# De_Embed.net
KiCad netlist of a schematic drawn in Altium Designer
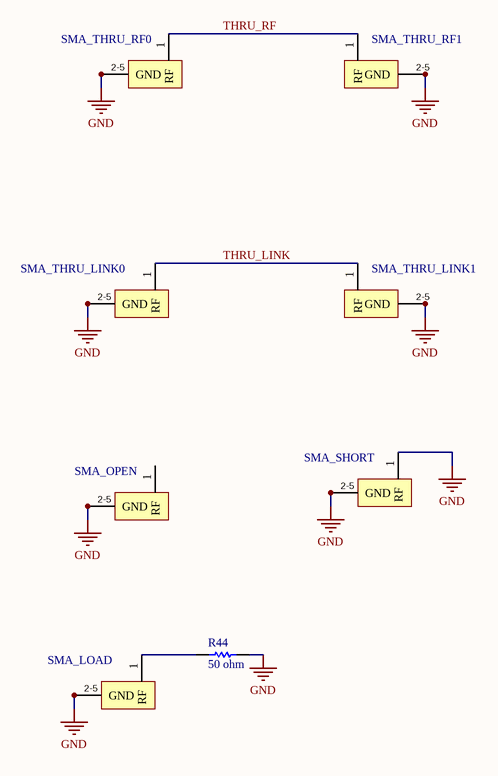
[diagram p0: De_Embed.SchDoc]

(export (version "E")
  (design (tool "Eeschema 10.0.6"))
  (components
    (comp (ref "R44")
      (value "50 ohm")
      (footprint "RES_0402")
      (description "RES SMD 50 OHM 0.1% 1/20W 0402")
      (fields (field (name "MANUFACTURER") "Vishay"))
      (libsource (lib "fader2_parts") (part "res 50 ohm 0402"))
    )
    (comp (ref "SMA_LOAD")
      (value "CONSMA001-SMD-G")
      (footprint "CON-SMA-SMD")
      (description "SMD SMA CONNECTOR")
      (libsource (lib "fader2_parts") (part "SURFACE MOUNT SMA CONNECTOR"))
    )
    (comp (ref "SMA_OPEN")
      (value "CONSMA001-SMD-G")
      (footprint "CON-SMA-SMD")
      (description "SMD SMA CONNECTOR")
      (libsource (lib "fader2_parts") (part "SURFACE MOUNT SMA CONNECTOR"))
    )
    (comp (ref "SMA_SHORT")
      (value "CONSMA001-SMD-G")
      (footprint "CON-SMA-SMD")
      (description "SMD SMA CONNECTOR")
      (libsource (lib "fader2_parts") (part "SURFACE MOUNT SMA CONNECTOR"))
    )
    (comp (ref "SMA_THRU_LINK0")
      (value "CONSMA001-SMD-G")
      (footprint "CON-SMA-SMD")
      (description "SMD SMA CONNECTOR")
      (libsource (lib "fader2_parts") (part "SURFACE MOUNT SMA CONNECTOR"))
    )
    (comp (ref "SMA_THRU_LINK1")
      (value "CONSMA001-SMD-G")
      (footprint "CON-SMA-SMD")
      (description "SMD SMA CONNECTOR")
      (libsource (lib "") (part "SURFACE MOUNT SMA CONNECTOR_1"))
    )
    (comp (ref "SMA_THRU_RF0")
      (value "CONSMA001-SMD-G")
      (footprint "CON-SMA-SMD")
      (description "SMD SMA CONNECTOR")
      (libsource (lib "fader2_parts") (part "SURFACE MOUNT SMA CONNECTOR"))
    )
    (comp (ref "SMA_THRU_RF1")
      (value "CONSMA001-SMD-G")
      (footprint "CON-SMA-SMD")
      (description "SMD SMA CONNECTOR")
      (libsource (lib "") (part "SURFACE MOUNT SMA CONNECTOR_1"))
    )
  )
  (nets
    (net (code "1") (name "/THRU_LINK") (class "Default")
      (node (ref "SMA_THRU_LINK0") (pin "1") (pinfunction "RF_1") (pintype "passive"))
      (node (ref "SMA_THRU_LINK1") (pin "1") (pinfunction "RF_1") (pintype "passive"))
    )
    (net (code "2") (name "/THRU_RF") (class "Default")
      (node (ref "SMA_THRU_RF0") (pin "1") (pinfunction "RF_1") (pintype "passive"))
      (node (ref "SMA_THRU_RF1") (pin "1") (pinfunction "RF_1") (pintype "passive"))
    )
    (net (code "3") (name "GND") (class "Default")
      (node (ref "R44") (pin "2") (pinfunction "BOT_2") (pintype "passive"))
      (node (ref "SMA_LOAD") (pin "2") (pinfunction "GND_2") (pintype "passive"))
      (node (ref "SMA_LOAD") (pin "3") (pinfunction "GND_3") (pintype "passive"))
      (node (ref "SMA_LOAD") (pin "4") (pinfunction "GND_4") (pintype "passive"))
      (node (ref "SMA_LOAD") (pin "5") (pinfunction "GND_5") (pintype "passive"))
      (node (ref "SMA_OPEN") (pin "2") (pinfunction "GND_2") (pintype "passive"))
      (node (ref "SMA_OPEN") (pin "3") (pinfunction "GND_3") (pintype "passive"))
      (node (ref "SMA_OPEN") (pin "4") (pinfunction "GND_4") (pintype "passive"))
      (node (ref "SMA_OPEN") (pin "5") (pinfunction "GND_5") (pintype "passive"))
      (node (ref "SMA_SHORT") (pin "1") (pinfunction "RF_1") (pintype "passive"))
      (node (ref "SMA_SHORT") (pin "2") (pinfunction "GND_2") (pintype "passive"))
      (node (ref "SMA_SHORT") (pin "3") (pinfunction "GND_3") (pintype "passive"))
      (node (ref "SMA_SHORT") (pin "4") (pinfunction "GND_4") (pintype "passive"))
      (node (ref "SMA_SHORT") (pin "5") (pinfunction "GND_5") (pintype "passive"))
      (node (ref "SMA_THRU_LINK0") (pin "2") (pinfunction "GND_2") (pintype "passive"))
      (node (ref "SMA_THRU_LINK0") (pin "3") (pinfunction "GND_3") (pintype "passive"))
      (node (ref "SMA_THRU_LINK0") (pin "4") (pinfunction "GND_4") (pintype "passive"))
      (node (ref "SMA_THRU_LINK0") (pin "5") (pinfunction "GND_5") (pintype "passive"))
      (node (ref "SMA_THRU_LINK1") (pin "2") (pinfunction "GND_2") (pintype "passive"))
      (node (ref "SMA_THRU_LINK1") (pin "3") (pinfunction "GND_3") (pintype "passive"))
      (node (ref "SMA_THRU_LINK1") (pin "4") (pinfunction "GND_4") (pintype "passive"))
      (node (ref "SMA_THRU_LINK1") (pin "5") (pinfunction "GND_5") (pintype "passive"))
      (node (ref "SMA_THRU_RF0") (pin "2") (pinfunction "GND_2") (pintype "passive"))
      (node (ref "SMA_THRU_RF0") (pin "3") (pinfunction "GND_3") (pintype "passive"))
      (node (ref "SMA_THRU_RF0") (pin "4") (pinfunction "GND_4") (pintype "passive"))
      (node (ref "SMA_THRU_RF0") (pin "5") (pinfunction "GND_5") (pintype "passive"))
      (node (ref "SMA_THRU_RF1") (pin "2") (pinfunction "GND_2") (pintype "passive"))
      (node (ref "SMA_THRU_RF1") (pin "3") (pinfunction "GND_3") (pintype "passive"))
      (node (ref "SMA_THRU_RF1") (pin "4") (pinfunction "GND_4") (pintype "passive"))
      (node (ref "SMA_THRU_RF1") (pin "5") (pinfunction "GND_5") (pintype "passive"))
    )
    (net (code "4") (name "Net-(R44-TOP)") (class "Default")
      (node (ref "R44") (pin "1") (pinfunction "TOP_1") (pintype "passive"))
      (node (ref "SMA_LOAD") (pin "1") (pinfunction "RF_1") (pintype "passive"))
    )
    (net (code "5") (name "unconnected-(SMA_OPEN-RF-Pad1)") (class "Default")
      (node (ref "SMA_OPEN") (pin "1") (pinfunction "RF_1") (pintype "passive"))
    )
  )
)
